# Rapide328smd.net
KiCad netlist of a schematic drawn in EAGLE
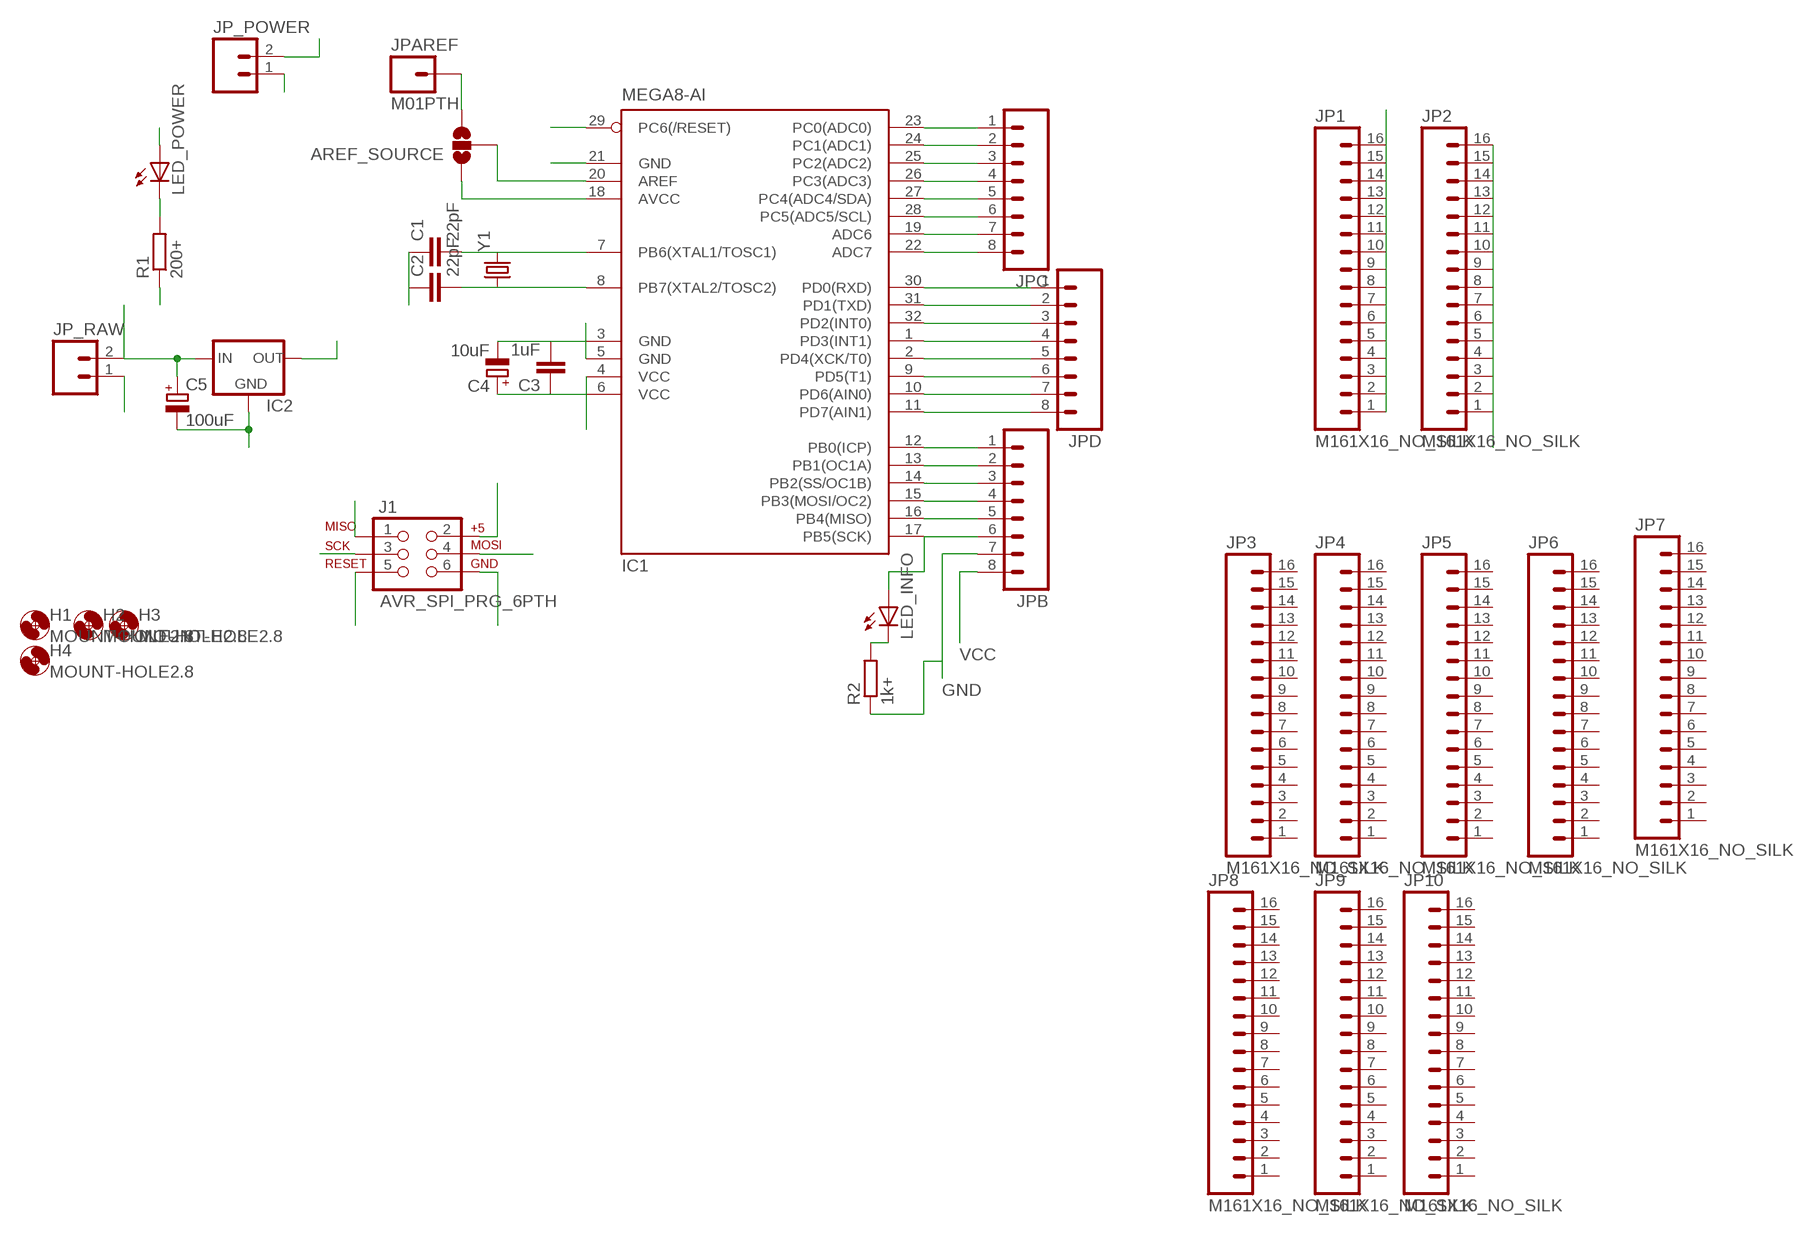
[diagram p0: schematic, sheet 1]

(export (version "E")
  (design (tool "Eeschema 10.0.6"))
  (components
    (comp (ref "AREF_SOURCE")
      (value "SOLDERJUMPER_2WAYPASTE1&2")
      (footprint "eagle-import:SJ_3_PASTE1&2")
      (libsource (lib "eagle-import") (part "SOLDERJUMPER_2WAYPASTE1&2"))
    )
    (comp (ref "C1")
      (value "22pF")
      (footprint "eagle-import:C025-024X044")
      (libsource (lib "eagle-import") (part "C-EU025-024X044"))
    )
    (comp (ref "C2")
      (value "22pF")
      (footprint "eagle-import:C025-024X044")
      (libsource (lib "eagle-import") (part "C-EU025-024X044"))
    )
    (comp (ref "C3")
      (value "1uF")
      (footprint "eagle-import:C025-024X044")
      (libsource (lib "eagle-import") (part "C-EU025-024X044"))
    )
    (comp (ref "C4")
      (value "10uF")
      (footprint "eagle-import:E2-5")
      (libsource (lib "eagle-import") (part "CPOL-EUE2-5"))
    )
    (comp (ref "C5")
      (value "100uF")
      (footprint "eagle-import:E2-5")
      (libsource (lib "eagle-import") (part "CPOL-EUE2-5"))
    )
    (comp (ref "H1")
      (value "MOUNT-HOLE2.8")
      (footprint "eagle-import:2,8")
      (libsource (lib "eagle-import") (part "MOUNT-HOLE2.8"))
    )
    (comp (ref "H2")
      (value "MOUNT-HOLE2.8")
      (footprint "eagle-import:2,8")
      (libsource (lib "eagle-import") (part "MOUNT-HOLE2.8"))
    )
    (comp (ref "H3")
      (value "MOUNT-HOLE2.8")
      (footprint "eagle-import:2,8")
      (libsource (lib "eagle-import") (part "MOUNT-HOLE2.8"))
    )
    (comp (ref "H4")
      (value "MOUNT-HOLE2.8")
      (footprint "eagle-import:2,8")
      (libsource (lib "eagle-import") (part "MOUNT-HOLE2.8"))
    )
    (comp (ref "IC1")
      (value "MEGA8-AI")
      (footprint "eagle-import:TQFP32-08")
      (fields (field (name "MPN") "ATMEGA8-16AU"))
      (libsource (lib "eagle-import") (part "MEGA8-AI"))
    )
    (comp (ref "IC2")
      (value "V_REG_78XXSINK")
      (footprint "eagle-import:TO220-IGO")
      (libsource (lib "eagle-import") (part "V_REG_78XXSINK"))
    )
    (comp (ref "J1")
      (value "AVR_SPI_PRG_6PTH")
      (footprint "eagle-import:2X3")
      (libsource (lib "eagle-import") (part "AVR_SPI_PRG_6PTH"))
    )
    (comp (ref "JP1")
      (value "M161X16_NO_SILK")
      (footprint "eagle-import:1X16_NO_SILK")
      (libsource (lib "eagle-import") (part "M161X16_NO_SILK"))
    )
    (comp (ref "JP2")
      (value "M161X16_NO_SILK")
      (footprint "eagle-import:1X16_NO_SILK")
      (libsource (lib "eagle-import") (part "M161X16_NO_SILK"))
    )
    (comp (ref "JP3")
      (value "M161X16_NO_SILK")
      (footprint "eagle-import:1X16_NO_SILK")
      (libsource (lib "eagle-import") (part "M161X16_NO_SILK"))
    )
    (comp (ref "JP4")
      (value "M161X16_NO_SILK")
      (footprint "eagle-import:1X16_NO_SILK")
      (libsource (lib "eagle-import") (part "M161X16_NO_SILK"))
    )
    (comp (ref "JP5")
      (value "M161X16_NO_SILK")
      (footprint "eagle-import:1X16_NO_SILK")
      (libsource (lib "eagle-import") (part "M161X16_NO_SILK"))
    )
    (comp (ref "JP6")
      (value "M161X16_NO_SILK")
      (footprint "eagle-import:1X16_NO_SILK")
      (libsource (lib "eagle-import") (part "M161X16_NO_SILK"))
    )
    (comp (ref "JP7")
      (value "M161X16_NO_SILK")
      (footprint "eagle-import:1X16_NO_SILK")
      (libsource (lib "eagle-import") (part "M161X16_NO_SILK"))
    )
    (comp (ref "JP8")
      (value "M161X16_NO_SILK")
      (footprint "eagle-import:1X16_NO_SILK")
      (libsource (lib "eagle-import") (part "M161X16_NO_SILK"))
    )
    (comp (ref "JP9")
      (value "M161X16_NO_SILK")
      (footprint "eagle-import:1X16_NO_SILK")
      (libsource (lib "eagle-import") (part "M161X16_NO_SILK"))
    )
    (comp (ref "JP10")
      (value "M161X16_NO_SILK")
      (footprint "eagle-import:1X16_NO_SILK")
      (libsource (lib "eagle-import") (part "M161X16_NO_SILK"))
    )
    (comp (ref "JPAREF")
      (value "M01PTH")
      (footprint "eagle-import:1X01")
      (libsource (lib "eagle-import") (part "M01PTH"))
    )
    (comp (ref "JPB")
      (value "M081X08")
      (footprint "eagle-import:1X08")
      (libsource (lib "eagle-import") (part "M081X08"))
    )
    (comp (ref "JPC")
      (value "M081X08")
      (footprint "eagle-import:1X08")
      (libsource (lib "eagle-import") (part "M081X08"))
    )
    (comp (ref "JPD")
      (value "M081X08")
      (footprint "eagle-import:1X08")
      (libsource (lib "eagle-import") (part "M081X08"))
    )
    (comp (ref "JP_POWER")
      (value "M02PTH3")
      (footprint "eagle-import:1X02_LONGPADS")
      (libsource (lib "eagle-import") (part "M02PTH3"))
    )
    (comp (ref "JP_RAW")
      (value "M02PTH3")
      (footprint "eagle-import:1X02_LONGPADS")
      (libsource (lib "eagle-import") (part "M02PTH3"))
    )
    (comp (ref "LED_INFO")
      (value "LEDKA-3528ASYC")
      (footprint "eagle-import:KA-3528ASYC")
      (libsource (lib "eagle-import") (part "LEDKA-3528ASYC"))
    )
    (comp (ref "LED_POWER")
      (value "LEDKA-3528ASYC")
      (footprint "eagle-import:KA-3528ASYC")
      (libsource (lib "eagle-import") (part "LEDKA-3528ASYC"))
    )
    (comp (ref "R1")
      (value "200+")
      (footprint "eagle-import:0204_7")
      (libsource (lib "eagle-import") (part "R-EU_0204/7"))
    )
    (comp (ref "R2")
      (value "1k+")
      (footprint "eagle-import:0204_5")
      (libsource (lib "eagle-import") (part "R-EU_0204/5"))
    )
    (comp (ref "Y1")
      (value "CRYSTALHC49UV")
      (footprint "eagle-import:HC49U-V")
      (libsource (lib "eagle-import") (part "CRYSTALHC49UV"))
    )
  )
  (nets
    (net (code "1") (name "/GND") (class "Default")
      (node (ref "C1") (pin "1") (pinfunction "1_1") (pintype "passive"))
      (node (ref "C2") (pin "1") (pinfunction "1_1") (pintype "passive"))
      (node (ref "C3") (pin "2") (pinfunction "2_2") (pintype "passive"))
      (node (ref "C4") (pin "-") (pinfunction "-_-") (pintype "passive"))
      (node (ref "C5") (pin "-") (pinfunction "-_-") (pintype "passive"))
      (node (ref "IC1") (pin "21") (pinfunction "GND_21") (pintype "power_in"))
      (node (ref "IC1") (pin "3") (pinfunction "GND_3") (pintype "power_in"))
      (node (ref "IC1") (pin "5") (pinfunction "GND_5") (pintype "power_in"))
      (node (ref "IC2") (pin "GND") (pinfunction "GND_GND") (pintype "input"))
      (node (ref "J1") (pin "6") (pinfunction "6_6") (pintype "passive"))
      (node (ref "JP2") (pin "1") (pinfunction "1_1") (pintype "passive"))
      (node (ref "JP2") (pin "10") (pinfunction "10_10") (pintype "passive"))
      (node (ref "JP2") (pin "11") (pinfunction "11_11") (pintype "passive"))
      (node (ref "JP2") (pin "12") (pinfunction "12_12") (pintype "passive"))
      (node (ref "JP2") (pin "13") (pinfunction "13_13") (pintype "passive"))
      (node (ref "JP2") (pin "14") (pinfunction "14_14") (pintype "passive"))
      (node (ref "JP2") (pin "15") (pinfunction "15_15") (pintype "passive"))
      (node (ref "JP2") (pin "16") (pinfunction "16_16") (pintype "passive"))
      (node (ref "JP2") (pin "2") (pinfunction "2_2") (pintype "passive"))
      (node (ref "JP2") (pin "3") (pinfunction "3_3") (pintype "passive"))
      (node (ref "JP2") (pin "4") (pinfunction "4_4") (pintype "passive"))
      (node (ref "JP2") (pin "5") (pinfunction "5_5") (pintype "passive"))
      (node (ref "JP2") (pin "6") (pinfunction "6_6") (pintype "passive"))
      (node (ref "JP2") (pin "7") (pinfunction "7_7") (pintype "passive"))
      (node (ref "JP2") (pin "8") (pinfunction "8_8") (pintype "passive"))
      (node (ref "JP2") (pin "9") (pinfunction "9_9") (pintype "passive"))
      (node (ref "JPB") (pin "7") (pinfunction "7_7") (pintype "passive"))
      (node (ref "JP_POWER") (pin "1") (pinfunction "1_1") (pintype "passive"))
      (node (ref "JP_RAW") (pin "1") (pinfunction "1_1") (pintype "passive"))
      (node (ref "R1") (pin "1") (pinfunction "1_1") (pintype "passive"))
      (node (ref "R2") (pin "1") (pinfunction "1_1") (pintype "passive"))
    )
    (net (code "2") (name "/MISO") (class "Default")
      (node (ref "IC1") (pin "16") (pinfunction "PB4(MISO)_16") (pintype "bidirectional"))
      (node (ref "J1") (pin "1") (pinfunction "1_1") (pintype "passive"))
      (node (ref "JPB") (pin "5") (pinfunction "5_5") (pintype "passive"))
    )
    (net (code "3") (name "/MOSI") (class "Default")
      (node (ref "IC1") (pin "15") (pinfunction "PB3(MOSI/OC2)_15") (pintype "bidirectional"))
      (node (ref "J1") (pin "4") (pinfunction "4_4") (pintype "passive"))
      (node (ref "JPB") (pin "4") (pinfunction "4_4") (pintype "passive"))
    )
    (net (code "4") (name "/RESET") (class "Default")
      (node (ref "IC1") (pin "29") (pinfunction "PC6(/RESET)_29") (pintype "bidirectional"))
      (node (ref "J1") (pin "5") (pinfunction "5_5") (pintype "passive"))
    )
    (net (code "5") (name "/SCK") (class "Default")
      (node (ref "IC1") (pin "17") (pinfunction "PB5(SCK)_17") (pintype "bidirectional"))
      (node (ref "J1") (pin "3") (pinfunction "3_3") (pintype "passive"))
      (node (ref "JPB") (pin "6") (pinfunction "6_6") (pintype "passive"))
      (node (ref "LED_INFO") (pin "A") (pinfunction "A_A") (pintype "passive"))
    )
    (net (code "6") (name "/VCC") (class "Default")
      (node (ref "AREF_SOURCE") (pin "1") (pinfunction "1_1") (pintype "passive"))
      (node (ref "C3") (pin "1") (pinfunction "1_1") (pintype "passive"))
      (node (ref "C4") (pin "+") (pinfunction "+_+") (pintype "passive"))
      (node (ref "IC1") (pin "18") (pinfunction "AVCC_18") (pintype "power_in"))
      (node (ref "IC1") (pin "4") (pinfunction "VCC_4") (pintype "power_in"))
      (node (ref "IC1") (pin "6") (pinfunction "VCC_6") (pintype "power_in"))
      (node (ref "IC2") (pin "OUT") (pinfunction "OUT_OUT") (pintype "output"))
      (node (ref "J1") (pin "2") (pinfunction "2_2") (pintype "passive"))
      (node (ref "JP1") (pin "1") (pinfunction "1_1") (pintype "passive"))
      (node (ref "JP1") (pin "10") (pinfunction "10_10") (pintype "passive"))
      (node (ref "JP1") (pin "11") (pinfunction "11_11") (pintype "passive"))
      (node (ref "JP1") (pin "12") (pinfunction "12_12") (pintype "passive"))
      (node (ref "JP1") (pin "13") (pinfunction "13_13") (pintype "passive"))
      (node (ref "JP1") (pin "14") (pinfunction "14_14") (pintype "passive"))
      (node (ref "JP1") (pin "15") (pinfunction "15_15") (pintype "passive"))
      (node (ref "JP1") (pin "16") (pinfunction "16_16") (pintype "passive"))
      (node (ref "JP1") (pin "2") (pinfunction "2_2") (pintype "passive"))
      (node (ref "JP1") (pin "3") (pinfunction "3_3") (pintype "passive"))
      (node (ref "JP1") (pin "4") (pinfunction "4_4") (pintype "passive"))
      (node (ref "JP1") (pin "5") (pinfunction "5_5") (pintype "passive"))
      (node (ref "JP1") (pin "6") (pinfunction "6_6") (pintype "passive"))
      (node (ref "JP1") (pin "7") (pinfunction "7_7") (pintype "passive"))
      (node (ref "JP1") (pin "8") (pinfunction "8_8") (pintype "passive"))
      (node (ref "JP1") (pin "9") (pinfunction "9_9") (pintype "passive"))
      (node (ref "JPB") (pin "8") (pinfunction "8_8") (pintype "passive"))
      (node (ref "JP_POWER") (pin "2") (pinfunction "2_2") (pintype "passive"))
      (node (ref "LED_POWER") (pin "A") (pinfunction "A_A") (pintype "passive"))
    )
    (net (code "7") (name "Net-(AREF_SOURCE-Pad3)") (class "Default")
      (node (ref "AREF_SOURCE") (pin "3") (pinfunction "3_3") (pintype "passive"))
      (node (ref "JPAREF") (pin "1") (pinfunction "1_1") (pintype "passive"))
    )
    (net (code "8") (name "Net-(C5-Pad+)") (class "Default")
      (node (ref "C5") (pin "+") (pinfunction "+_+") (pintype "passive"))
      (node (ref "IC2") (pin "IN") (pinfunction "IN_IN") (pintype "input"))
      (node (ref "JP_RAW") (pin "2") (pinfunction "2_2") (pintype "passive"))
    )
    (net (code "9") (name "Net-(IC1-ADC6)") (class "Default")
      (node (ref "IC1") (pin "19") (pinfunction "ADC6_19") (pintype "bidirectional"))
      (node (ref "JPC") (pin "7") (pinfunction "7_7") (pintype "passive"))
    )
    (net (code "10") (name "Net-(IC1-ADC7)") (class "Default")
      (node (ref "IC1") (pin "22") (pinfunction "ADC7_22") (pintype "bidirectional"))
      (node (ref "JPC") (pin "8") (pinfunction "8_8") (pintype "passive"))
    )
    (net (code "11") (name "Net-(IC1-AREF)") (class "Default")
      (node (ref "AREF_SOURCE") (pin "2") (pinfunction "2_2") (pintype "passive"))
      (node (ref "IC1") (pin "20") (pinfunction "AREF_20") (pintype "passive"))
    )
    (net (code "12") (name "Net-(IC1-PB0(ICP))") (class "Default")
      (node (ref "IC1") (pin "12") (pinfunction "PB0(ICP)_12") (pintype "bidirectional"))
      (node (ref "JPB") (pin "1") (pinfunction "1_1") (pintype "passive"))
    )
    (net (code "13") (name "Net-(IC1-PB1(OC1A))") (class "Default")
      (node (ref "IC1") (pin "13") (pinfunction "PB1(OC1A)_13") (pintype "bidirectional"))
      (node (ref "JPB") (pin "2") (pinfunction "2_2") (pintype "passive"))
    )
    (net (code "14") (name "Net-(IC1-PB2(SS{slash}OC1B))") (class "Default")
      (node (ref "IC1") (pin "14") (pinfunction "PB2(SS/OC1B)_14") (pintype "bidirectional"))
      (node (ref "JPB") (pin "3") (pinfunction "3_3") (pintype "passive"))
    )
    (net (code "15") (name "Net-(IC1-PB6(XTAL1{slash}TOSC1))") (class "Default")
      (node (ref "C1") (pin "2") (pinfunction "2_2") (pintype "passive"))
      (node (ref "IC1") (pin "7") (pinfunction "PB6(XTAL1/TOSC1)_7") (pintype "bidirectional"))
      (node (ref "Y1") (pin "2") (pinfunction "2_2") (pintype "passive"))
    )
    (net (code "16") (name "Net-(IC1-PB7(XTAL2{slash}TOSC2))") (class "Default")
      (node (ref "C2") (pin "2") (pinfunction "2_2") (pintype "passive"))
      (node (ref "IC1") (pin "8") (pinfunction "PB7(XTAL2/TOSC2)_8") (pintype "bidirectional"))
      (node (ref "Y1") (pin "1") (pinfunction "1_1") (pintype "passive"))
    )
    (net (code "17") (name "Net-(IC1-PC0(ADC0))") (class "Default")
      (node (ref "IC1") (pin "23") (pinfunction "PC0(ADC0)_23") (pintype "bidirectional"))
      (node (ref "JPC") (pin "1") (pinfunction "1_1") (pintype "passive"))
    )
    (net (code "18") (name "Net-(IC1-PC1(ADC1))") (class "Default")
      (node (ref "IC1") (pin "24") (pinfunction "PC1(ADC1)_24") (pintype "bidirectional"))
      (node (ref "JPC") (pin "2") (pinfunction "2_2") (pintype "passive"))
    )
    (net (code "19") (name "Net-(IC1-PC2(ADC2))") (class "Default")
      (node (ref "IC1") (pin "25") (pinfunction "PC2(ADC2)_25") (pintype "bidirectional"))
      (node (ref "JPC") (pin "3") (pinfunction "3_3") (pintype "passive"))
    )
    (net (code "20") (name "Net-(IC1-PC3(ADC3))") (class "Default")
      (node (ref "IC1") (pin "26") (pinfunction "PC3(ADC3)_26") (pintype "bidirectional"))
      (node (ref "JPC") (pin "4") (pinfunction "4_4") (pintype "passive"))
    )
    (net (code "21") (name "Net-(IC1-PC4(ADC4{slash}SDA))") (class "Default")
      (node (ref "IC1") (pin "27") (pinfunction "PC4(ADC4/SDA)_27") (pintype "bidirectional"))
      (node (ref "JPC") (pin "5") (pinfunction "5_5") (pintype "passive"))
    )
    (net (code "22") (name "Net-(IC1-PC5(ADC5{slash}SCL))") (class "Default")
      (node (ref "IC1") (pin "28") (pinfunction "PC5(ADC5/SCL)_28") (pintype "bidirectional"))
      (node (ref "JPC") (pin "6") (pinfunction "6_6") (pintype "passive"))
    )
    (net (code "23") (name "Net-(IC1-PD0(RXD))") (class "Default")
      (node (ref "IC1") (pin "30") (pinfunction "PD0(RXD)_30") (pintype "bidirectional"))
      (node (ref "JPD") (pin "1") (pinfunction "1_1") (pintype "passive"))
    )
    (net (code "24") (name "Net-(IC1-PD1(TXD))") (class "Default")
      (node (ref "IC1") (pin "31") (pinfunction "PD1(TXD)_31") (pintype "bidirectional"))
      (node (ref "JPD") (pin "2") (pinfunction "2_2") (pintype "passive"))
    )
    (net (code "25") (name "Net-(IC1-PD2(INT0))") (class "Default")
      (node (ref "IC1") (pin "32") (pinfunction "PD2(INT0)_32") (pintype "bidirectional"))
      (node (ref "JPD") (pin "3") (pinfunction "3_3") (pintype "passive"))
    )
    (net (code "26") (name "Net-(IC1-PD3(INT1))") (class "Default")
      (node (ref "IC1") (pin "1") (pinfunction "PD3(INT1)_1") (pintype "bidirectional"))
      (node (ref "JPD") (pin "4") (pinfunction "4_4") (pintype "passive"))
    )
    (net (code "27") (name "Net-(IC1-PD4(XCK{slash}T0))") (class "Default")
      (node (ref "IC1") (pin "2") (pinfunction "PD4(XCK/T0)_2") (pintype "bidirectional"))
      (node (ref "JPD") (pin "5") (pinfunction "5_5") (pintype "passive"))
    )
    (net (code "28") (name "Net-(IC1-PD5(T1))") (class "Default")
      (node (ref "IC1") (pin "9") (pinfunction "PD5(T1)_9") (pintype "bidirectional"))
      (node (ref "JPD") (pin "6") (pinfunction "6_6") (pintype "passive"))
    )
    (net (code "29") (name "Net-(IC1-PD6(AIN0))") (class "Default")
      (node (ref "IC1") (pin "10") (pinfunction "PD6(AIN0)_10") (pintype "bidirectional"))
      (node (ref "JPD") (pin "7") (pinfunction "7_7") (pintype "passive"))
    )
    (net (code "30") (name "Net-(IC1-PD7(AIN1))") (class "Default")
      (node (ref "IC1") (pin "11") (pinfunction "PD7(AIN1)_11") (pintype "bidirectional"))
      (node (ref "JPD") (pin "8") (pinfunction "8_8") (pintype "passive"))
    )
    (net (code "31") (name "Net-(LED_INFO-PadC)") (class "Default")
      (node (ref "LED_INFO") (pin "C") (pinfunction "C_C") (pintype "passive"))
      (node (ref "R2") (pin "2") (pinfunction "2_2") (pintype "passive"))
    )
    (net (code "32") (name "Net-(LED_POWER-PadC)") (class "Default")
      (node (ref "LED_POWER") (pin "C") (pinfunction "C_C") (pintype "passive"))
      (node (ref "R1") (pin "2") (pinfunction "2_2") (pintype "passive"))
    )
    (net (code "33") (name "unconnected-(JP3-Pad1)") (class "Default")
      (node (ref "JP3") (pin "1") (pinfunction "1_1") (pintype "passive"))
    )
    (net (code "34") (name "unconnected-(JP3-Pad2)") (class "Default")
      (node (ref "JP3") (pin "2") (pinfunction "2_2") (pintype "passive"))
    )
    (net (code "35") (name "unconnected-(JP3-Pad3)") (class "Default")
      (node (ref "JP3") (pin "3") (pinfunction "3_3") (pintype "passive"))
    )
    (net (code "36") (name "unconnected-(JP3-Pad4)") (class "Default")
      (node (ref "JP3") (pin "4") (pinfunction "4_4") (pintype "passive"))
    )
    (net (code "37") (name "unconnected-(JP3-Pad5)") (class "Default")
      (node (ref "JP3") (pin "5") (pinfunction "5_5") (pintype "passive"))
    )
    (net (code "38") (name "unconnected-(JP3-Pad6)") (class "Default")
      (node (ref "JP3") (pin "6") (pinfunction "6_6") (pintype "passive"))
    )
    (net (code "39") (name "unconnected-(JP3-Pad7)") (class "Default")
      (node (ref "JP3") (pin "7") (pinfunction "7_7") (pintype "passive"))
    )
    (net (code "40") (name "unconnected-(JP3-Pad8)") (class "Default")
      (node (ref "JP3") (pin "8") (pinfunction "8_8") (pintype "passive"))
    )
    (net (code "41") (name "unconnected-(JP3-Pad9)") (class "Default")
      (node (ref "JP3") (pin "9") (pinfunction "9_9") (pintype "passive"))
    )
    (net (code "42") (name "unconnected-(JP3-Pad10)") (class "Default")
      (node (ref "JP3") (pin "10") (pinfunction "10_10") (pintype "passive"))
    )
    (net (code "43") (name "unconnected-(JP3-Pad11)") (class "Default")
      (node (ref "JP3") (pin "11") (pinfunction "11_11") (pintype "passive"))
    )
    (net (code "44") (name "unconnected-(JP3-Pad12)") (class "Default")
      (node (ref "JP3") (pin "12") (pinfunction "12_12") (pintype "passive"))
    )
    (net (code "45") (name "unconnected-(JP3-Pad13)") (class "Default")
      (node (ref "JP3") (pin "13") (pinfunction "13_13") (pintype "passive"))
    )
    (net (code "46") (name "unconnected-(JP3-Pad14)") (class "Default")
      (node (ref "JP3") (pin "14") (pinfunction "14_14") (pintype "passive"))
    )
    (net (code "47") (name "unconnected-(JP3-Pad15)") (class "Default")
      (node (ref "JP3") (pin "15") (pinfunction "15_15") (pintype "passive"))
    )
    (net (code "48") (name "unconnected-(JP3-Pad16)") (class "Default")
      (node (ref "JP3") (pin "16") (pinfunction "16_16") (pintype "passive"))
    )
    (net (code "49") (name "unconnected-(JP4-Pad1)") (class "Default")
      (node (ref "JP4") (pin "1") (pinfunction "1_1") (pintype "passive"))
    )
    (net (code "50") (name "unconnected-(JP4-Pad2)") (class "Default")
      (node (ref "JP4") (pin "2") (pinfunction "2_2") (pintype "passive"))
    )
    (net (code "51") (name "unconnected-(JP4-Pad3)") (class "Default")
      (node (ref "JP4") (pin "3") (pinfunction "3_3") (pintype "passive"))
    )
    (net (code "52") (name "unconnected-(JP4-Pad4)") (class "Default")
      (node (ref "JP4") (pin "4") (pinfunction "4_4") (pintype "passive"))
    )
    (net (code "53") (name "unconnected-(JP4-Pad5)") (class "Default")
      (node (ref "JP4") (pin "5") (pinfunction "5_5") (pintype "passive"))
    )
    (net (code "54") (name "unconnected-(JP4-Pad6)") (class "Default")
      (node (ref "JP4") (pin "6") (pinfunction "6_6") (pintype "passive"))
    )
    (net (code "55") (name "unconnected-(JP4-Pad7)") (class "Default")
      (node (ref "JP4") (pin "7") (pinfunction "7_7") (pintype "passive"))
    )
    (net (code "56") (name "unconnected-(JP4-Pad8)") (class "Default")
      (node (ref "JP4") (pin "8") (pinfunction "8_8") (pintype "passive"))
    )
    (net (code "57") (name "unconnected-(JP4-Pad9)") (class "Default")
      (node (ref "JP4") (pin "9") (pinfunction "9_9") (pintype "passive"))
    )
    (net (code "58") (name "unconnected-(JP4-Pad10)") (class "Default")
      (node (ref "JP4") (pin "10") (pinfunction "10_10") (pintype "passive"))
    )
    (net (code "59") (name "unconnected-(JP4-Pad11)") (class "Default")
      (node (ref "JP4") (pin "11") (pinfunction "11_11") (pintype "passive"))
    )
    (net (code "60") (name "unconnected-(JP4-Pad12)") (class "Default")
      (node (ref "JP4") (pin "12") (pinfunction "12_12") (pintype "passive"))
    )
    (net (code "61") (name "unconnected-(JP4-Pad13)") (class "Default")
      (node (ref "JP4") (pin "13") (pinfunction "13_13") (pintype "passive"))
    )
    (net (code "62") (name "unconnected-(JP4-Pad14)") (class "Default")
      (node (ref "JP4") (pin "14") (pinfunction "14_14") (pintype "passive"))
    )
    (net (code "63") (name "unconnected-(JP4-Pad15)") (class "Default")
      (node (ref "JP4") (pin "15") (pinfunction "15_15") (pintype "passive"))
    )
    (net (code "64") (name "unconnected-(JP4-Pad16)") (class "Default")
      (node (ref "JP4") (pin "16") (pinfunction "16_16") (pintype "passive"))
    )
    (net (code "65") (name "unconnected-(JP5-Pad1)") (class "Default")
      (node (ref "JP5") (pin "1") (pinfunction "1_1") (pintype "passive"))
    )
    (net (code "66") (name "unconnected-(JP5-Pad2)") (class "Default")
      (node (ref "JP5") (pin "2") (pinfunction "2_2") (pintype "passive"))
    )
    (net (code "67") (name "unconnected-(JP5-Pad3)") (class "Default")
      (node (ref "JP5") (pin "3") (pinfunction "3_3") (pintype "passive"))
    )
    (net (code "68") (name "unconnected-(JP5-Pad4)") (class "Default")
      (node (ref "JP5") (pin "4") (pinfunction "4_4") (pintype "passive"))
    )
    (net (code "69") (name "unconnected-(JP5-Pad5)") (class "Default")
      (node (ref "JP5") (pin "5") (pinfunction "5_5") (pintype "passive"))
    )
    (net (code "70") (name "unconnected-(JP5-Pad6)") (class "Default")
      (node (ref "JP5") (pin "6") (pinfunction "6_6") (pintype "passive"))
    )
    (net (code "71") (name "unconnected-(JP5-Pad7)") (class "Default")
      (node (ref "JP5") (pin "7") (pinfunction "7_7") (pintype "passive"))
    )
    (net (code "72") (name "unconnected-(JP5-Pad8)") (class "Default")
      (node (ref "JP5") (pin "8") (pinfunction "8_8") (pintype "passive"))
    )
    (net (code "73") (name "unconnected-(JP5-Pad9)") (class "Default")
      (node (ref "JP5") (pin "9") (pinfunction "9_9") (pintype "passive"))
    )
    (net (code "74") (name "unconnected-(JP5-Pad10)") (class "Default")
      (node (ref "JP5") (pin "10") (pinfunction "10_10") (pintype "passive"))
    )
    (net (code "75") (name "unconnected-(JP5-Pad11)") (class "Default")
      (node (ref "JP5") (pin "11") (pinfunction "11_11") (pintype "passive"))
    )
    (net (code "76") (name "unconnected-(JP5-Pad12)") (class "Default")
      (node (ref "JP5") (pin "12") (pinfunction "12_12") (pintype "passive"))
    )
    (net (code "77") (name "unconnected-(JP5-Pad13)") (class "Default")
      (node (ref "JP5") (pin "13") (pinfunction "13_13") (pintype "passive"))
    )
    (net (code "78") (name "unconnected-(JP5-Pad14)") (class "Default")
      (node (ref "JP5") (pin "14") (pinfunction "14_14") (pintype "passive"))
    )
    (net (code "79") (name "unconnected-(JP5-Pad15)") (class "Default")
      (node (ref "JP5") (pin "15") (pinfunction "15_15") (pintype "passive"))
    )
    (net (code "80") (name "unconnected-(JP5-Pad16)") (class "Default")
      (node (ref "JP5") (pin "16") (pinfunction "16_16") (pintype "passive"))
    )
    (net (code "81") (name "unconnected-(JP6-Pad1)") (class "Default")
      (node (ref "JP6") (pin "1") (pinfunction "1_1") (pintype "passive"))
    )
    (net (code "82") (name "unconnected-(JP6-Pad2)") (class "Default")
      (node (ref "JP6") (pin "2") (pinfunction "2_2") (pintype "passive"))
    )
    (net (code "83") (name "unconnected-(JP6-Pad3)") (class "Default")
      (node (ref "JP6") (pin "3") (pinfunction "3_3") (pintype "passive"))
    )
    (net (code "84") (name "unconnected-(JP6-Pad4)") (class "Default")
      (node (ref "JP6") (pin "4") (pinfunction "4_4") (pintype "passive"))
    )
    (net (code "85") (name "unconnected-(JP6-Pad5)") (class "Default")
      (node (ref "JP6") (pin "5") (pinfunction "5_5") (pintype "passive"))
    )
    (net (code "86") (name "unconnected-(JP6-Pad6)") (class "Default")
      (node (ref "JP6") (pin "6") (pinfunction "6_6") (pintype "passive"))
    )
    (net (code "87") (name "unconnected-(JP6-Pad7)") (class "Default")
      (node (ref "JP6") (pin "7") (pinfunction "7_7") (pintype "passive"))
    )
    (net (code "88") (name "unconnected-(JP6-Pad8)") (class "Default")
      (node (ref "JP6") (pin "8") (pinfunction "8_8") (pintype "passive"))
    )
    (net (code "89") (name "unconnected-(JP6-Pad9)") (class "Default")
      (node (ref "JP6") (pin "9") (pinfunction "9_9") (pintype "passive"))
    )
    (net (code "90") (name "unconnected-(JP6-Pad10)") (class "Default")
      (node (ref "JP6") (pin "10") (pinfunction "10_10") (pintype "passive"))
    )
    (net (code "91") (name "unconnected-(JP6-Pad11)") (class "Default")
      (node (ref "JP6") (pin "11") (pinfunction "11_11") (pintype "passive"))
    )
    (net (code "92") (name "unconnected-(JP6-Pad12)") (class "Default")
      (node (ref "JP6") (pin "12") (pinfunction "12_12") (pintype "passive"))
    )
    (net (code "93") (name "unconnected-(JP6-Pad13)") (class "Default")
      (node (ref "JP6") (pin "13") (pinfunction "13_13") (pintype "passive"))
    )
    (net (code "94") (name "unconnected-(JP6-Pad14)") (class "Default")
      (node (ref "JP6") (pin "14") (pinfunction "14_14") (pintype "passive"))
    )
    (net (code "95") (name "unconnected-(JP6-Pad15)") (class "Default")
      (node (ref "JP6") (pin "15") (pinfunction "15_15") (pintype "passive"))
    )
    (net (code "96") (name "unconnected-(JP6-Pad16)") (class "Default")
      (node (ref "JP6") (pin "16") (pinfunction "16_16") (pintype "passive"))
    )
    (net (code "97") (name "unconnected-(JP7-Pad1)") (class "Default")
      (node (ref "JP7") (pin "1") (pinfunction "1_1") (pintype "passive"))
    )
    (net (code "98") (name "unconnected-(JP7-Pad2)") (class "Default")
      (node (ref "JP7") (pin "2") (pinfunction "2_2") (pintype "passive"))
    )
    (net (code "99") (name "unconnected-(JP7-Pad3)") (class "Default")
      (node (ref "JP7") (pin "3") (pinfunction "3_3") (pintype "passive"))
    )
    (net (code "100") (name "unconnected-(JP7-Pad4)") (class "Default")
      (node (ref "JP7") (pin "4") (pinfunction "4_4") (pintype "passive"))
    )
    (net (code "101") (name "unconnected-(JP7-Pad5)") (class "Default")
      (node (ref "JP7") (pin "5") (pinfunction "5_5") (pintype "passive"))
    )
    (net (code "102") (name "unconnected-(JP7-Pad6)") (class "Default")
      (node (ref "JP7") (pin "6") (pinfunction "6_6") (pintype "passive"))
    )
    (net (code "103") (name "unconnected-(JP7-Pad7)") (class "Default")
      (node (ref "JP7") (pin "7") (pinfunction "7_7") (pintype "passive"))
    )
    (net (code "104") (name "unconnected-(JP7-Pad8)") (class "Default")
      (node (ref "JP7") (pin "8") (pinfunction "8_8") (pintype "passive"))
    )
    (net (code "105") (name "unconnected-(JP7-Pad9)") (class "Default")
      (node (ref "JP7") (pin "9") (pinfunction "9_9") (pintype "passive"))
    )
    (net (code "106") (name "unconnected-(JP7-Pad10)") (class "Default")
      (node (ref "JP7") (pin "10") (pinfunction "10_10") (pintype "passive"))
    )
    (net (code "107") (name "unconnected-(JP7-Pad11)") (class "Default")
      (node (ref "JP7") (pin "11") (pinfunction "11_11") (pintype "passive"))
    )
    (net (code "108") (name "unconnected-(JP7-Pad12)") (class "Default")
      (node (ref "JP7") (pin "12") (pinfunction "12_12") (pintype "passive"))
    )
    (net (code "109") (name "unconnected-(JP7-Pad13)") (class "Default")
      (node (ref "JP7") (pin "13") (pinfunction "13_13") (pintype "passive"))
    )
    (net (code "110") (name "unconnected-(JP7-Pad14)") (class "Default")
      (node (ref "JP7") (pin "14") (pinfunction "14_14") (pintype "passive"))
    )
    (net (code "111") (name "unconnected-(JP7-Pad15)") (class "Default")
      (node (ref "JP7") (pin "15") (pinfunction "15_15") (pintype "passive"))
    )
    (net (code "112") (name "unconnected-(JP7-Pad16)") (class "Default")
      (node (ref "JP7") (pin "16") (pinfunction "16_16") (pintype "passive"))
    )
    (net (code "113") (name "unconnected-(JP8-Pad1)") (class "Default")
      (node (ref "JP8") (pin "1") (pinfunction "1_1") (pintype "passive"))
    )
    (net (code "114") (name "unconnected-(JP8-Pad2)") (class "Default")
      (node (ref "JP8") (pin "2") (pinfunction "2_2") (pintype "passive"))
    )
    (net (code "115") (name "unconnected-(JP8-Pad3)") (class "Default")
      (node (ref "JP8") (pin "3") (pinfunction "3_3") (pintype "passive"))
    )
    (net (code "116") (name "unconnected-(JP8-Pad4)") (class "Default")
      (node (ref "JP8") (pin "4") (pinfunction "4_4") (pintype "passive"))
    )
    (net (code "117") (name "unconnected-(JP8-Pad5)") (class "Default")
      (node (ref "JP8") (pin "5") (pinfunction "5_5") (pintype "passive"))
    )
    (net (code "118") (name "unconnected-(JP8-Pad6)") (class "Default")
      (node (ref "JP8") (pin "6") (pinfunction "6_6") (pintype "passive"))
    )
    (net (code "119") (name "unconnected-(JP8-Pad7)") (class "Default")
      (node (ref "JP8") (pin "7") (pinfunction "7_7") (pintype "passive"))
    )
    (net (code "120") (name "unconnected-(JP8-Pad8)") (class "Default")
      (node (ref "JP8") (pin "8") (pinfunction "8_8") (pintype "passive"))
    )
    (net (code "121") (name "unconnected-(JP8-Pad9)") (class "Default")
      (node (ref "JP8") (pin "9") (pinfunction "9_9") (pintype "passive"))
    )
    (net (code "122") (name "unconnected-(JP8-Pad10)") (class "Default")
      (node (ref "JP8") (pin "10") (pinfunction "10_10") (pintype "passive"))
    )
    (net (code "123") (name "unconnected-(JP8-Pad11)") (class "Default")
      (node (ref "JP8") (pin "11") (pinfunction "11_11") (pintype "passive"))
    )
    (net (code "124") (name "unconnected-(JP8-Pad12)") (class "Default")
      (node (ref "JP8") (pin "12") (pinfunction "12_12") (pintype "passive"))
    )
    (net (code "125") (name "unconnected-(JP8-Pad13)") (class "Default")
      (node (ref "JP8") (pin "13") (pinfunction "13_13") (pintype "passive"))
    )
    (net (code "126") (name "unconnected-(JP8-Pad14)") (class "Default")
      (node (ref "JP8") (pin "14") (pinfunction "14_14") (pintype "passive"))
    )
    (net (code "127") (name "unconnected-(JP8-Pad15)") (class "Default")
      (node (ref "JP8") (pin "15") (pinfunction "15_15") (pintype "passive"))
    )
    (net (code "128") (name "unconnected-(JP8-Pad16)") (class "Default")
      (node (ref "JP8") (pin "16") (pinfunction "16_16") (pintype "passive"))
    )
    (net (code "129") (name "unconnected-(JP9-Pad1)") (class "Default")
      (node (ref "JP9") (pin "1") (pinfunction "1_1") (pintype "passive"))
    )
    (net (code "130") (name "unconnected-(JP9-Pad2)") (class "Default")
      (node (ref "JP9") (pin "2") (pinfunction "2_2") (pintype "passive"))
    )
    (net (code "131") (name "unconnected-(JP9-Pad3)") (class "Default")
      (node (ref "JP9") (pin "3") (pinfunction "3_3") (pintype "passive"))
    )
    (net (code "132") (name "unconnected-(JP9-Pad4)") (class "Default")
      (node (ref "JP9") (pin "4") (pinfunction "4_4") (pintype "passive"))
    )
    (net (code "133") (name "unconnected-(JP9-Pad5)") (class "Default")
      (node (ref "JP9") (pin "5") (pinfunction "5_5") (pintype "passive"))
    )
    (net (code "134") (name "unconnected-(JP9-Pad6)") (class "Default")
      (node (ref "JP9") (pin "6") (pinfunction "6_6") (pintype "passive"))
    )
    (net (code "135") (name "unconnected-(JP9-Pad7)") (class "Default")
      (node (ref "JP9") (pin "7") (pinfunction "7_7") (pintype "passive"))
    )
    (net (code "136") (name "unconnected-(JP9-Pad8)") (class "Default")
      (node (ref "JP9") (pin "8") (pinfunction "8_8") (pintype "passive"))
    )
    (net (code "137") (name "unconnected-(JP9-Pad9)") (class "Default")
      (node (ref "JP9") (pin "9") (pinfunction "9_9") (pintype "passive"))
    )
    (net (code "138") (name "unconnected-(JP9-Pad10)") (class "Default")
      (node (ref "JP9") (pin "10") (pinfunction "10_10") (pintype "passive"))
    )
    (net (code "139") (name "unconnected-(JP9-Pad11)") (class "Default")
      (node (ref "JP9") (pin "11") (pinfunction "11_11") (pintype "passive"))
    )
    (net (code "140") (name "unconnected-(JP9-Pad12)") (class "Default")
      (node (ref "JP9") (pin "12") (pinfunction "12_12") (pintype "passive"))
    )
    (net (code "141") (name "unconnected-(JP9-Pad13)") (class "Default")
      (node (ref "JP9") (pin "13") (pinfunction "13_13") (pintype "passive"))
    )
    (net (code "142") (name "unconnected-(JP9-Pad14)") (class "Default")
      (node (ref "JP9") (pin "14") (pinfunction "14_14") (pintype "passive"))
    )
    (net (code "143") (name "unconnected-(JP9-Pad15)") (class "Default")
      (node (ref "JP9") (pin "15") (pinfunction "15_15") (pintype "passive"))
    )
    (net (code "144") (name "unconnected-(JP9-Pad16)") (class "Default")
      (node (ref "JP9") (pin "16") (pinfunction "16_16") (pintype "passive"))
    )
    (net (code "145") (name "unconnected-(JP10-Pad1)") (class "Default")
      (node (ref "JP10") (pin "1") (pinfunction "1_1") (pintype "passive"))
    )
    (net (code "146") (name "unconnected-(JP10-Pad2)") (class "Default")
      (node (ref "JP10") (pin "2") (pinfunction "2_2") (pintype "passive"))
    )
    (net (code "147") (name "unconnected-(JP10-Pad3)") (class "Default")
      (node (ref "JP10") (pin "3") (pinfunction "3_3") (pintype "passive"))
    )
    (net (code "148") (name "unconnected-(JP10-Pad4)") (class "Default")
      (node (ref "JP10") (pin "4") (pinfunction "4_4") (pintype "passive"))
    )
    (net (code "149") (name "unconnected-(JP10-Pad5)") (class "Default")
      (node (ref "JP10") (pin "5") (pinfunction "5_5") (pintype "passive"))
    )
    (net (code "150") (name "unconnected-(JP10-Pad6)") (class "Default")
      (node (ref "JP10") (pin "6") (pinfunction "6_6") (pintype "passive"))
    )
    (net (code "151") (name "unconnected-(JP10-Pad7)") (class "Default")
      (node (ref "JP10") (pin "7") (pinfunction "7_7") (pintype "passive"))
    )
    (net (code "152") (name "unconnected-(JP10-Pad8)") (class "Default")
      (node (ref "JP10") (pin "8") (pinfunction "8_8") (pintype "passive"))
    )
    (net (code "153") (name "unconnected-(JP10-Pad9)") (class "Default")
      (node (ref "JP10") (pin "9") (pinfunction "9_9") (pintype "passive"))
    )
    (net (code "154") (name "unconnected-(JP10-Pad10)") (class "Default")
      (node (ref "JP10") (pin "10") (pinfunction "10_10") (pintype "passive"))
    )
    (net (code "155") (name "unconnected-(JP10-Pad11)") (class "Default")
      (node (ref "JP10") (pin "11") (pinfunction "11_11") (pintype "passive"))
    )
    (net (code "156") (name "unconnected-(JP10-Pad12)") (class "Default")
      (node (ref "JP10") (pin "12") (pinfunction "12_12") (pintype "passive"))
    )
    (net (code "157") (name "unconnected-(JP10-Pad13)") (class "Default")
      (node (ref "JP10") (pin "13") (pinfunction "13_13") (pintype "passive"))
    )
    (net (code "158") (name "unconnected-(JP10-Pad14)") (class "Default")
      (node (ref "JP10") (pin "14") (pinfunction "14_14") (pintype "passive"))
    )
    (net (code "159") (name "unconnected-(JP10-Pad15)") (class "Default")
      (node (ref "JP10") (pin "15") (pinfunction "15_15") (pintype "passive"))
    )
    (net (code "160") (name "unconnected-(JP10-Pad16)") (class "Default")
      (node (ref "JP10") (pin "16") (pinfunction "16_16") (pintype "passive"))
    )
  )
)
